# hurf1_schematic.net
KiCad netlist of a schematic drawn in EAGLE
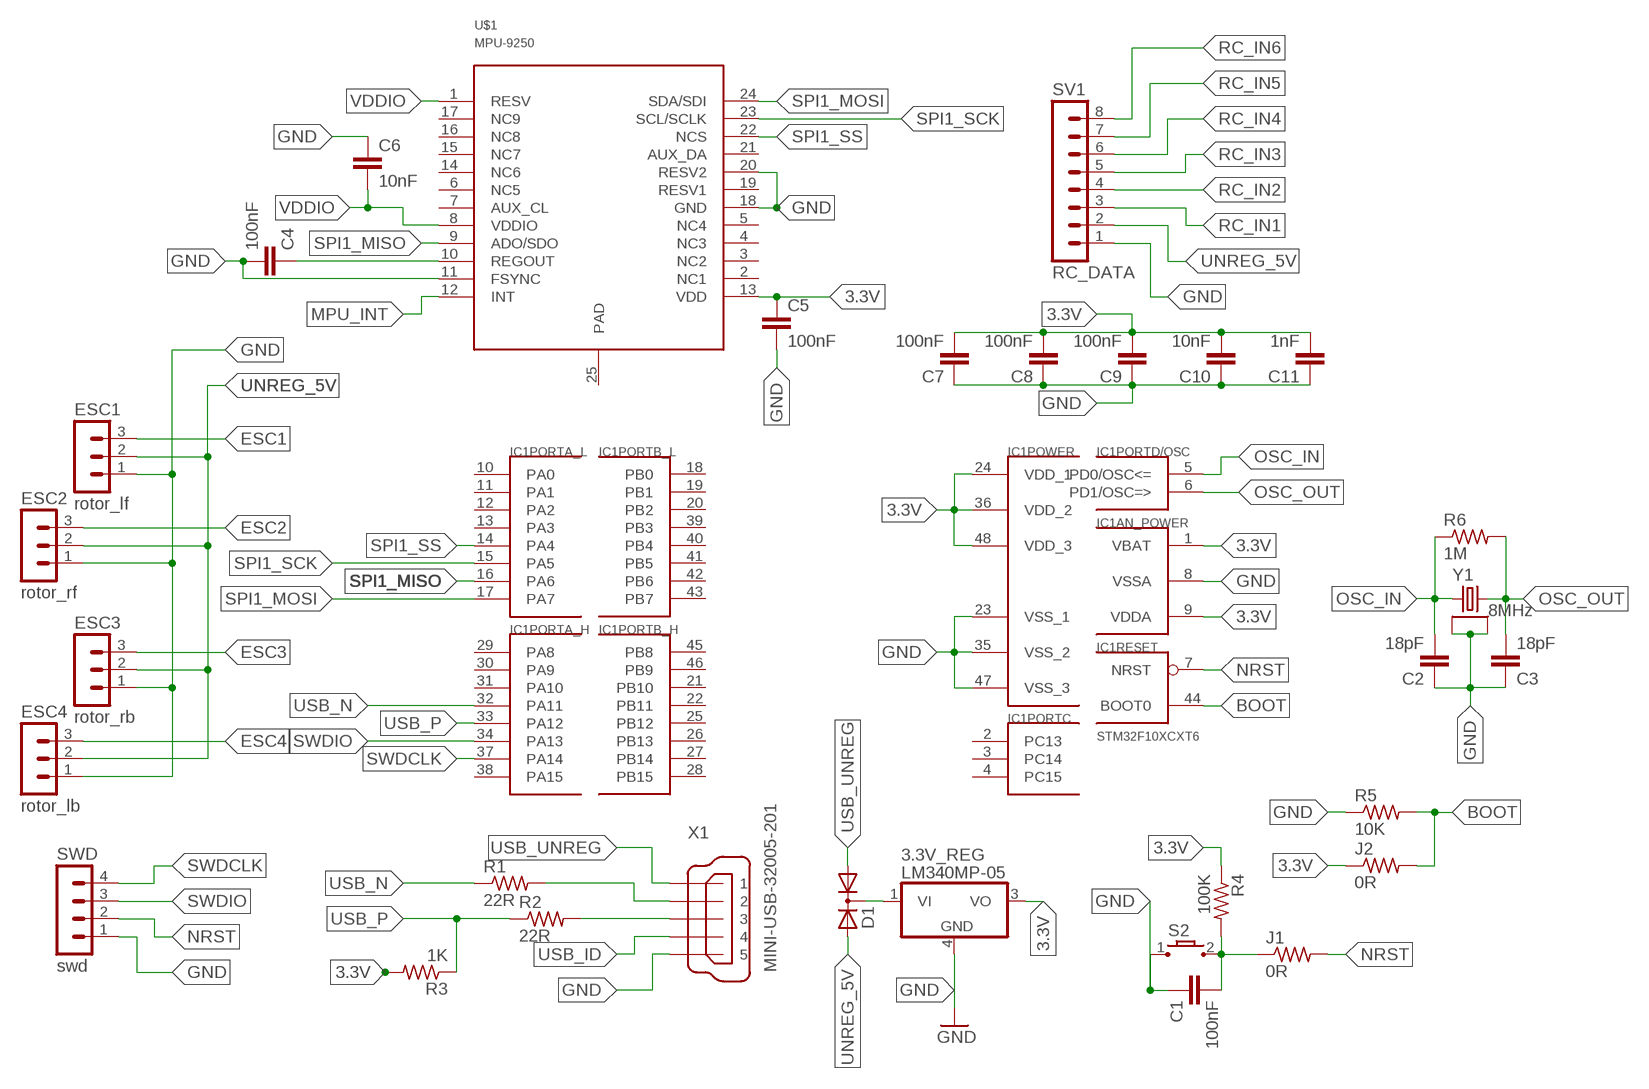
[diagram p0: schematic, sheet 1]

(export (version "E")
  (design (tool "Eeschema 10.0.6"))
  (components
    (comp (ref "3.3V_REG")
      (value "LM340MP-05")
      (footprint "eagle-import:SOT223")
      (libsource (lib "eagle-import") (part "LM340?-MP05"))
    )
    (comp (ref "C1")
      (value "100nF")
      (footprint "eagle-import:C0805K")
      (libsource (lib "eagle-import") (part "C-EUC0805K"))
    )
    (comp (ref "C2")
      (value "18pF")
      (footprint "eagle-import:C0805K")
      (libsource (lib "eagle-import") (part "C-EUC0805K"))
    )
    (comp (ref "C3")
      (value "18pF")
      (footprint "eagle-import:C0805K")
      (libsource (lib "eagle-import") (part "C-EUC0805K"))
    )
    (comp (ref "C4")
      (value "100nF")
      (footprint "eagle-import:C0805K")
      (libsource (lib "eagle-import") (part "C-EUC0805K"))
    )
    (comp (ref "C5")
      (value "100nF")
      (footprint "eagle-import:C0805K")
      (libsource (lib "eagle-import") (part "C-EUC0805K"))
    )
    (comp (ref "C6")
      (value "10nF")
      (footprint "eagle-import:C0805K")
      (libsource (lib "eagle-import") (part "C-EUC0805K"))
    )
    (comp (ref "C7")
      (value "100nF")
      (footprint "eagle-import:C0805K")
      (libsource (lib "eagle-import") (part "C-EUC0805K"))
    )
    (comp (ref "C8")
      (value "100nF")
      (footprint "eagle-import:C0805K")
      (libsource (lib "eagle-import") (part "C-EUC0805K"))
    )
    (comp (ref "C9")
      (value "100nF")
      (footprint "eagle-import:C0805K")
      (libsource (lib "eagle-import") (part "C-EUC0805K"))
    )
    (comp (ref "C10")
      (value "10nF")
      (footprint "eagle-import:C0805K")
      (libsource (lib "eagle-import") (part "C-EUC0805K"))
    )
    (comp (ref "C11")
      (value "1nF")
      (footprint "eagle-import:C0805K")
      (libsource (lib "eagle-import") (part "C-EUC0805K"))
    )
    (comp (ref "D1")
      (value "DIODE-2AC|CASOT23")
      (footprint "eagle-import:SOT23")
      (libsource (lib "eagle-import") (part "DIODE-2AC|CASOT23"))
    )
    (comp (ref "ESC1")
      (value "rotor_lf")
      (footprint "eagle-import:MA03-1")
      (libsource (lib "eagle-import") (part "MA03-1"))
    )
    (comp (ref "ESC2")
      (value "rotor_rf")
      (footprint "eagle-import:MA03-1")
      (libsource (lib "eagle-import") (part "MA03-1"))
    )
    (comp (ref "ESC3")
      (value "rotor_rb")
      (footprint "eagle-import:MA03-1")
      (libsource (lib "eagle-import") (part "MA03-1"))
    )
    (comp (ref "ESC4")
      (value "rotor_lb")
      (footprint "eagle-import:MA03-1")
      (libsource (lib "eagle-import") (part "MA03-1"))
    )
    (comp (ref "IC1")
      (value "STM32F10XCXT6")
      (footprint "eagle-import:TQFP48")
      (libsource (lib "eagle-import") (part "STM32F10XCXT6"))
    )
    (comp (ref "J1")
      (value "0R")
      (footprint "eagle-import:M0805")
      (libsource (lib "eagle-import") (part "R-US_M0805"))
    )
    (comp (ref "J2")
      (value "0R")
      (footprint "eagle-import:M0805")
      (libsource (lib "eagle-import") (part "R-US_M0805"))
    )
    (comp (ref "R1")
      (value "22R")
      (footprint "eagle-import:M0805")
      (libsource (lib "eagle-import") (part "R-US_M0805"))
    )
    (comp (ref "R2")
      (value "22R")
      (footprint "eagle-import:M0805")
      (libsource (lib "eagle-import") (part "R-US_M0805"))
    )
    (comp (ref "R3")
      (value "1K")
      (footprint "eagle-import:M0805")
      (libsource (lib "eagle-import") (part "R-US_M0805"))
    )
    (comp (ref "R4")
      (value "100K")
      (footprint "eagle-import:M0805")
      (libsource (lib "eagle-import") (part "R-US_M0805"))
    )
    (comp (ref "R5")
      (value "10K")
      (footprint "eagle-import:M0805")
      (libsource (lib "eagle-import") (part "R-US_M0805"))
    )
    (comp (ref "R6")
      (value "1M")
      (footprint "eagle-import:M0805")
      (libsource (lib "eagle-import") (part "R-US_M0805"))
    )
    (comp (ref "S2")
      (value "TL3302-G")
      (footprint "eagle-import:TL3302_GULL_WING")
      (libsource (lib "eagle-import") (part "TL3302-G"))
    )
    (comp (ref "SV1")
      (value "RC_DATA")
      (footprint "eagle-import:MA08-1")
      (libsource (lib "eagle-import") (part "MA08-1"))
    )
    (comp (ref "SWD")
      (value "swd")
      (footprint "eagle-import:MA04-1")
      (libsource (lib "eagle-import") (part "MA04-1"))
    )
    (comp (ref "U$1")
      (value "MPU-9250")
      (footprint "eagle-import:LEAD-QFN24")
      (libsource (lib "eagle-import") (part "MPU-9250"))
    )
    (comp (ref "X1")
      (value "MINI-USB-32005-201")
      (footprint "eagle-import:32005-201")
      (libsource (lib "eagle-import") (part "MINI-USB-32005-201"))
    )
    (comp (ref "Y1")
      (value "8MHz")
      (footprint "eagle-import:GSX-531")
      (libsource (lib "eagle-import") (part "GSX-531"))
    )
  )
  (nets
    (net (code "1") (name "3.3V") (class "Default")
      (node (ref "3.3V_REG") (pin "3") (pinfunction "VO_3") (pintype "passive"))
      (node (ref "C10") (pin "2") (pinfunction "2_2") (pintype "passive"))
      (node (ref "C11") (pin "2") (pinfunction "2_2") (pintype "passive"))
      (node (ref "C5") (pin "1") (pinfunction "1_1") (pintype "passive"))
      (node (ref "C7") (pin "2") (pinfunction "2_2") (pintype "passive"))
      (node (ref "C8") (pin "2") (pinfunction "2_2") (pintype "passive"))
      (node (ref "C9") (pin "2") (pinfunction "2_2") (pintype "passive"))
      (node (ref "IC1") (pin "1") (pinfunction "VBAT_1") (pintype "power_in"))
      (node (ref "IC1") (pin "24") (pinfunction "VDD_1_24") (pintype "power_in"))
      (node (ref "IC1") (pin "36") (pinfunction "VDD_2_36") (pintype "power_in"))
      (node (ref "IC1") (pin "48") (pinfunction "VDD_3_48") (pintype "power_in"))
      (node (ref "IC1") (pin "9") (pinfunction "VDDA_9") (pintype "power_in"))
      (node (ref "J2") (pin "1") (pinfunction "1_1") (pintype "passive"))
      (node (ref "R3") (pin "2") (pinfunction "2_2") (pintype "passive"))
      (node (ref "R4") (pin "1") (pinfunction "1_1") (pintype "passive"))
      (node (ref "U$1") (pin "13") (pinfunction "VDD_13") (pintype "bidirectional"))
    )
    (net (code "2") (name "BOOT") (class "Default")
      (node (ref "IC1") (pin "44") (pinfunction "BOOT0_44") (pintype "input"))
      (node (ref "J2") (pin "2") (pinfunction "2_2") (pintype "passive"))
      (node (ref "R5") (pin "2") (pinfunction "2_2") (pintype "passive"))
    )
    (net (code "3") (name "ESC1") (class "Default")
      (node (ref "ESC1") (pin "3") (pinfunction "3_3") (pintype "passive"))
    )
    (net (code "4") (name "ESC2") (class "Default")
      (node (ref "ESC2") (pin "3") (pinfunction "3_3") (pintype "passive"))
    )
    (net (code "5") (name "ESC3") (class "Default")
      (node (ref "ESC3") (pin "3") (pinfunction "3_3") (pintype "passive"))
    )
    (net (code "6") (name "ESC4") (class "Default")
      (node (ref "ESC4") (pin "3") (pinfunction "3_3") (pintype "passive"))
    )
    (net (code "7") (name "GND") (class "Default")
      (node (ref "3.3V_REG") (pin "4") (pinfunction "GND_4") (pintype "passive"))
      (node (ref "C1") (pin "1") (pinfunction "1_1") (pintype "passive"))
      (node (ref "C10") (pin "1") (pinfunction "1_1") (pintype "passive"))
      (node (ref "C11") (pin "1") (pinfunction "1_1") (pintype "passive"))
      (node (ref "C2") (pin "1") (pinfunction "1_1") (pintype "passive"))
      (node (ref "C3") (pin "1") (pinfunction "1_1") (pintype "passive"))
      (node (ref "C4") (pin "2") (pinfunction "2_2") (pintype "passive"))
      (node (ref "C5") (pin "2") (pinfunction "2_2") (pintype "passive"))
      (node (ref "C6") (pin "1") (pinfunction "1_1") (pintype "passive"))
      (node (ref "C7") (pin "1") (pinfunction "1_1") (pintype "passive"))
      (node (ref "C8") (pin "1") (pinfunction "1_1") (pintype "passive"))
      (node (ref "C9") (pin "1") (pinfunction "1_1") (pintype "passive"))
      (node (ref "ESC1") (pin "1") (pinfunction "1_1") (pintype "passive"))
      (node (ref "ESC2") (pin "1") (pinfunction "1_1") (pintype "passive"))
      (node (ref "ESC3") (pin "1") (pinfunction "1_1") (pintype "passive"))
      (node (ref "ESC4") (pin "1") (pinfunction "1_1") (pintype "passive"))
      (node (ref "IC1") (pin "23") (pinfunction "VSS_1_23") (pintype "power_in"))
      (node (ref "IC1") (pin "35") (pinfunction "VSS_2_35") (pintype "power_in"))
      (node (ref "IC1") (pin "47") (pinfunction "VSS_3_47") (pintype "power_in"))
      (node (ref "IC1") (pin "8") (pinfunction "VSSA_8") (pintype "power_in"))
      (node (ref "R5") (pin "1") (pinfunction "1_1") (pintype "passive"))
      (node (ref "S2") (pin "1") (pinfunction "1_1") (pintype "passive"))
      (node (ref "SV1") (pin "1") (pinfunction "1_1") (pintype "passive"))
      (node (ref "SWD") (pin "1") (pinfunction "1_1") (pintype "passive"))
      (node (ref "U$1") (pin "11") (pinfunction "FSYNC_11") (pintype "bidirectional"))
      (node (ref "U$1") (pin "18") (pinfunction "GND_18") (pintype "bidirectional"))
      (node (ref "U$1") (pin "20") (pinfunction "RESV2_20") (pintype "bidirectional"))
      (node (ref "X1") (pin "5") (pinfunction "5_5") (pintype "passive"))
      (node (ref "Y1") (pin "2") (pinfunction "2_2") (pintype "passive"))
      (node (ref "Y1") (pin "4") (pinfunction "4_4") (pintype "passive"))
    )
    (net (code "8") (name "MPU_INT") (class "Default")
      (node (ref "U$1") (pin "12") (pinfunction "INT_12") (pintype "bidirectional"))
    )
    (net (code "9") (name "NRST") (class "Default")
      (node (ref "IC1") (pin "7") (pinfunction "NRST_7") (pintype "input"))
      (node (ref "J1") (pin "2") (pinfunction "2_2") (pintype "passive"))
      (node (ref "SWD") (pin "2") (pinfunction "2_2") (pintype "passive"))
    )
    (net (code "10") (name "Net-(3.3V_REG-VI)") (class "Default")
      (node (ref "3.3V_REG") (pin "1") (pinfunction "VI_1") (pintype "input"))
      (node (ref "D1") (pin "3") (pinfunction "C_3") (pintype "passive"))
    )
    (net (code "11") (name "Net-(C1-Pad2)") (class "Default")
      (node (ref "C1") (pin "2") (pinfunction "2_2") (pintype "passive"))
      (node (ref "J1") (pin "1") (pinfunction "1_1") (pintype "passive"))
      (node (ref "R4") (pin "2") (pinfunction "2_2") (pintype "passive"))
      (node (ref "S2") (pin "2") (pinfunction "2_2") (pintype "passive"))
    )
    (net (code "12") (name "Net-(R1-Pad2)") (class "Default")
      (node (ref "R1") (pin "2") (pinfunction "2_2") (pintype "passive"))
      (node (ref "X1") (pin "2") (pinfunction "2_2") (pintype "passive"))
    )
    (net (code "13") (name "Net-(R2-Pad2)") (class "Default")
      (node (ref "R2") (pin "2") (pinfunction "2_2") (pintype "passive"))
      (node (ref "X1") (pin "3") (pinfunction "3_3") (pintype "passive"))
    )
    (net (code "14") (name "Net-(U$1-REGOUT)") (class "Default")
      (node (ref "C4") (pin "1") (pinfunction "1_1") (pintype "passive"))
      (node (ref "U$1") (pin "10") (pinfunction "REGOUT_10") (pintype "bidirectional"))
    )
    (net (code "15") (name "OSC_IN") (class "Default")
      (node (ref "C2") (pin "2") (pinfunction "2_2") (pintype "passive"))
      (node (ref "IC1") (pin "5") (pinfunction "PD0/OSC<=_5") (pintype "bidirectional"))
      (node (ref "R6") (pin "1") (pinfunction "1_1") (pintype "passive"))
      (node (ref "Y1") (pin "1") (pinfunction "1_1") (pintype "passive"))
    )
    (net (code "16") (name "OSC_OUT") (class "Default")
      (node (ref "C3") (pin "2") (pinfunction "2_2") (pintype "passive"))
      (node (ref "IC1") (pin "6") (pinfunction "PD1/OSC=>_6") (pintype "bidirectional"))
      (node (ref "R6") (pin "2") (pinfunction "2_2") (pintype "passive"))
      (node (ref "Y1") (pin "3") (pinfunction "3_3") (pintype "passive"))
    )
    (net (code "17") (name "RC_IN1") (class "Default")
      (node (ref "SV1") (pin "3") (pinfunction "3_3") (pintype "passive"))
    )
    (net (code "18") (name "RC_IN2") (class "Default")
      (node (ref "SV1") (pin "4") (pinfunction "4_4") (pintype "passive"))
    )
    (net (code "19") (name "RC_IN3") (class "Default")
      (node (ref "SV1") (pin "5") (pinfunction "5_5") (pintype "passive"))
    )
    (net (code "20") (name "RC_IN4") (class "Default")
      (node (ref "SV1") (pin "6") (pinfunction "6_6") (pintype "passive"))
    )
    (net (code "21") (name "RC_IN5") (class "Default")
      (node (ref "SV1") (pin "7") (pinfunction "7_7") (pintype "passive"))
    )
    (net (code "22") (name "RC_IN6") (class "Default")
      (node (ref "SV1") (pin "8") (pinfunction "8_8") (pintype "passive"))
    )
    (net (code "23") (name "SPI1_MISO") (class "Default")
      (node (ref "IC1") (pin "16") (pinfunction "PA6_16") (pintype "bidirectional"))
      (node (ref "U$1") (pin "9") (pinfunction "ADO/SDO_9") (pintype "bidirectional"))
    )
    (net (code "24") (name "SPI1_MOSI") (class "Default")
      (node (ref "IC1") (pin "17") (pinfunction "PA7_17") (pintype "bidirectional"))
      (node (ref "U$1") (pin "24") (pinfunction "SDA/SDI_24") (pintype "bidirectional"))
    )
    (net (code "25") (name "SPI1_SCK") (class "Default")
      (node (ref "IC1") (pin "15") (pinfunction "PA5_15") (pintype "bidirectional"))
      (node (ref "U$1") (pin "23") (pinfunction "SCL/SCLK_23") (pintype "bidirectional"))
    )
    (net (code "26") (name "SPI1_SS") (class "Default")
      (node (ref "IC1") (pin "14") (pinfunction "PA4_14") (pintype "bidirectional"))
      (node (ref "U$1") (pin "22") (pinfunction "NCS_22") (pintype "bidirectional"))
    )
    (net (code "27") (name "SWDCLK") (class "Default")
      (node (ref "IC1") (pin "37") (pinfunction "PA14_37") (pintype "bidirectional"))
      (node (ref "SWD") (pin "4") (pinfunction "4_4") (pintype "passive"))
    )
    (net (code "28") (name "SWDIO") (class "Default")
      (node (ref "IC1") (pin "34") (pinfunction "PA13_34") (pintype "bidirectional"))
      (node (ref "SWD") (pin "3") (pinfunction "3_3") (pintype "passive"))
    )
    (net (code "29") (name "UNREG_5V") (class "Default")
      (node (ref "D1") (pin "2") (pinfunction "A2_2") (pintype "passive"))
      (node (ref "ESC1") (pin "2") (pinfunction "2_2") (pintype "passive"))
      (node (ref "ESC2") (pin "2") (pinfunction "2_2") (pintype "passive"))
      (node (ref "ESC3") (pin "2") (pinfunction "2_2") (pintype "passive"))
      (node (ref "ESC4") (pin "2") (pinfunction "2_2") (pintype "passive"))
      (node (ref "SV1") (pin "2") (pinfunction "2_2") (pintype "passive"))
    )
    (net (code "30") (name "USB_ID") (class "Default")
      (node (ref "X1") (pin "4") (pinfunction "4_4") (pintype "passive"))
    )
    (net (code "31") (name "USB_N") (class "Default")
      (node (ref "IC1") (pin "32") (pinfunction "PA11_32") (pintype "bidirectional"))
      (node (ref "R1") (pin "1") (pinfunction "1_1") (pintype "passive"))
    )
    (net (code "32") (name "USB_P") (class "Default")
      (node (ref "IC1") (pin "33") (pinfunction "PA12_33") (pintype "bidirectional"))
      (node (ref "R2") (pin "1") (pinfunction "1_1") (pintype "passive"))
      (node (ref "R3") (pin "1") (pinfunction "1_1") (pintype "passive"))
    )
    (net (code "33") (name "USB_UNREG") (class "Default")
      (node (ref "D1") (pin "1") (pinfunction "A1_1") (pintype "passive"))
      (node (ref "X1") (pin "1") (pinfunction "1_1") (pintype "passive"))
    )
    (net (code "34") (name "VDDIO") (class "Default")
      (node (ref "C6") (pin "2") (pinfunction "2_2") (pintype "passive"))
      (node (ref "U$1") (pin "1") (pinfunction "RESV_1") (pintype "bidirectional"))
      (node (ref "U$1") (pin "8") (pinfunction "VDDIO_8") (pintype "bidirectional"))
    )
    (net (code "35") (name "unconnected-(IC1B-PA8-Pad29)") (class "Default")
      (node (ref "IC1") (pin "29") (pinfunction "PA8_29") (pintype "bidirectional"))
    )
    (net (code "36") (name "unconnected-(IC1B-PA9-Pad30)") (class "Default")
      (node (ref "IC1") (pin "30") (pinfunction "PA9_30") (pintype "bidirectional"))
    )
    (net (code "37") (name "unconnected-(IC1B-PA10-Pad31)") (class "Default")
      (node (ref "IC1") (pin "31") (pinfunction "PA10_31") (pintype "bidirectional"))
    )
    (net (code "38") (name "unconnected-(IC1B-PA15-Pad38)") (class "Default")
      (node (ref "IC1") (pin "38") (pinfunction "PA15_38") (pintype "bidirectional"))
    )
    (net (code "39") (name "unconnected-(IC1C-PA0-Pad10)") (class "Default")
      (node (ref "IC1") (pin "10") (pinfunction "PA0_10") (pintype "bidirectional"))
    )
    (net (code "40") (name "unconnected-(IC1C-PA1-Pad11)") (class "Default")
      (node (ref "IC1") (pin "11") (pinfunction "PA1_11") (pintype "bidirectional"))
    )
    (net (code "41") (name "unconnected-(IC1C-PA2-Pad12)") (class "Default")
      (node (ref "IC1") (pin "12") (pinfunction "PA2_12") (pintype "bidirectional"))
    )
    (net (code "42") (name "unconnected-(IC1C-PA3-Pad13)") (class "Default")
      (node (ref "IC1") (pin "13") (pinfunction "PA3_13") (pintype "bidirectional"))
    )
    (net (code "43") (name "unconnected-(IC1D-PB8-Pad45)") (class "Default")
      (node (ref "IC1") (pin "45") (pinfunction "PB8_45") (pintype "bidirectional"))
    )
    (net (code "44") (name "unconnected-(IC1D-PB9-Pad46)") (class "Default")
      (node (ref "IC1") (pin "46") (pinfunction "PB9_46") (pintype "bidirectional"))
    )
    (net (code "45") (name "unconnected-(IC1D-PB10-Pad21)") (class "Default")
      (node (ref "IC1") (pin "21") (pinfunction "PB10_21") (pintype "bidirectional"))
    )
    (net (code "46") (name "unconnected-(IC1D-PB11-Pad22)") (class "Default")
      (node (ref "IC1") (pin "22") (pinfunction "PB11_22") (pintype "bidirectional"))
    )
    (net (code "47") (name "unconnected-(IC1D-PB12-Pad25)") (class "Default")
      (node (ref "IC1") (pin "25") (pinfunction "PB12_25") (pintype "bidirectional"))
    )
    (net (code "48") (name "unconnected-(IC1D-PB13-Pad26)") (class "Default")
      (node (ref "IC1") (pin "26") (pinfunction "PB13_26") (pintype "bidirectional"))
    )
    (net (code "49") (name "unconnected-(IC1D-PB14-Pad27)") (class "Default")
      (node (ref "IC1") (pin "27") (pinfunction "PB14_27") (pintype "bidirectional"))
    )
    (net (code "50") (name "unconnected-(IC1D-PB15-Pad28)") (class "Default")
      (node (ref "IC1") (pin "28") (pinfunction "PB15_28") (pintype "bidirectional"))
    )
    (net (code "51") (name "unconnected-(IC1E-PB0-Pad18)") (class "Default")
      (node (ref "IC1") (pin "18") (pinfunction "PB0_18") (pintype "bidirectional"))
    )
    (net (code "52") (name "unconnected-(IC1E-PB1-Pad19)") (class "Default")
      (node (ref "IC1") (pin "19") (pinfunction "PB1_19") (pintype "bidirectional"))
    )
    (net (code "53") (name "unconnected-(IC1E-PB2-Pad20)") (class "Default")
      (node (ref "IC1") (pin "20") (pinfunction "PB2_20") (pintype "bidirectional"))
    )
    (net (code "54") (name "unconnected-(IC1E-PB3-Pad39)") (class "Default")
      (node (ref "IC1") (pin "39") (pinfunction "PB3_39") (pintype "bidirectional"))
    )
    (net (code "55") (name "unconnected-(IC1E-PB4-Pad40)") (class "Default")
      (node (ref "IC1") (pin "40") (pinfunction "PB4_40") (pintype "bidirectional"))
    )
    (net (code "56") (name "unconnected-(IC1E-PB5-Pad41)") (class "Default")
      (node (ref "IC1") (pin "41") (pinfunction "PB5_41") (pintype "bidirectional"))
    )
    (net (code "57") (name "unconnected-(IC1E-PB6-Pad42)") (class "Default")
      (node (ref "IC1") (pin "42") (pinfunction "PB6_42") (pintype "bidirectional"))
    )
    (net (code "58") (name "unconnected-(IC1E-PB7-Pad43)") (class "Default")
      (node (ref "IC1") (pin "43") (pinfunction "PB7_43") (pintype "bidirectional"))
    )
    (net (code "59") (name "unconnected-(IC1F-PC13-Pad2)") (class "Default")
      (node (ref "IC1") (pin "2") (pinfunction "PC13_2") (pintype "bidirectional"))
    )
    (net (code "60") (name "unconnected-(IC1F-PC14-Pad3)") (class "Default")
      (node (ref "IC1") (pin "3") (pinfunction "PC14_3") (pintype "bidirectional"))
    )
    (net (code "61") (name "unconnected-(IC1F-PC15-Pad4)") (class "Default")
      (node (ref "IC1") (pin "4") (pinfunction "PC15_4") (pintype "bidirectional"))
    )
    (net (code "62") (name "unconnected-(U$1-AUX_CL-Pad7)") (class "Default")
      (node (ref "U$1") (pin "7") (pinfunction "AUX_CL_7") (pintype "bidirectional"))
    )
    (net (code "63") (name "unconnected-(U$1-AUX_DA-Pad21)") (class "Default")
      (node (ref "U$1") (pin "21") (pinfunction "AUX_DA_21") (pintype "bidirectional"))
    )
    (net (code "64") (name "unconnected-(U$1-NC1-Pad2)") (class "Default")
      (node (ref "U$1") (pin "2") (pinfunction "NC1_2") (pintype "bidirectional"))
    )
    (net (code "65") (name "unconnected-(U$1-NC2-Pad3)") (class "Default")
      (node (ref "U$1") (pin "3") (pinfunction "NC2_3") (pintype "bidirectional"))
    )
    (net (code "66") (name "unconnected-(U$1-NC3-Pad4)") (class "Default")
      (node (ref "U$1") (pin "4") (pinfunction "NC3_4") (pintype "bidirectional"))
    )
    (net (code "67") (name "unconnected-(U$1-NC4-Pad5)") (class "Default")
      (node (ref "U$1") (pin "5") (pinfunction "NC4_5") (pintype "bidirectional"))
    )
    (net (code "68") (name "unconnected-(U$1-NC5-Pad6)") (class "Default")
      (node (ref "U$1") (pin "6") (pinfunction "NC5_6") (pintype "bidirectional"))
    )
    (net (code "69") (name "unconnected-(U$1-NC6-Pad14)") (class "Default")
      (node (ref "U$1") (pin "14") (pinfunction "NC6_14") (pintype "bidirectional"))
    )
    (net (code "70") (name "unconnected-(U$1-NC7-Pad15)") (class "Default")
      (node (ref "U$1") (pin "15") (pinfunction "NC7_15") (pintype "bidirectional"))
    )
    (net (code "71") (name "unconnected-(U$1-NC8-Pad16)") (class "Default")
      (node (ref "U$1") (pin "16") (pinfunction "NC8_16") (pintype "bidirectional"))
    )
    (net (code "72") (name "unconnected-(U$1-NC9-Pad17)") (class "Default")
      (node (ref "U$1") (pin "17") (pinfunction "NC9_17") (pintype "bidirectional"))
    )
    (net (code "73") (name "unconnected-(U$1-PAD-Pad25)") (class "Default")
      (node (ref "U$1") (pin "25") (pinfunction "PAD_25") (pintype "bidirectional"))
    )
    (net (code "74") (name "unconnected-(U$1-RESV1-Pad19)") (class "Default")
      (node (ref "U$1") (pin "19") (pinfunction "RESV1_19") (pintype "bidirectional"))
    )
  )
)
